# PIRprotov1.net
KiCad netlist of a schematic drawn in EAGLE
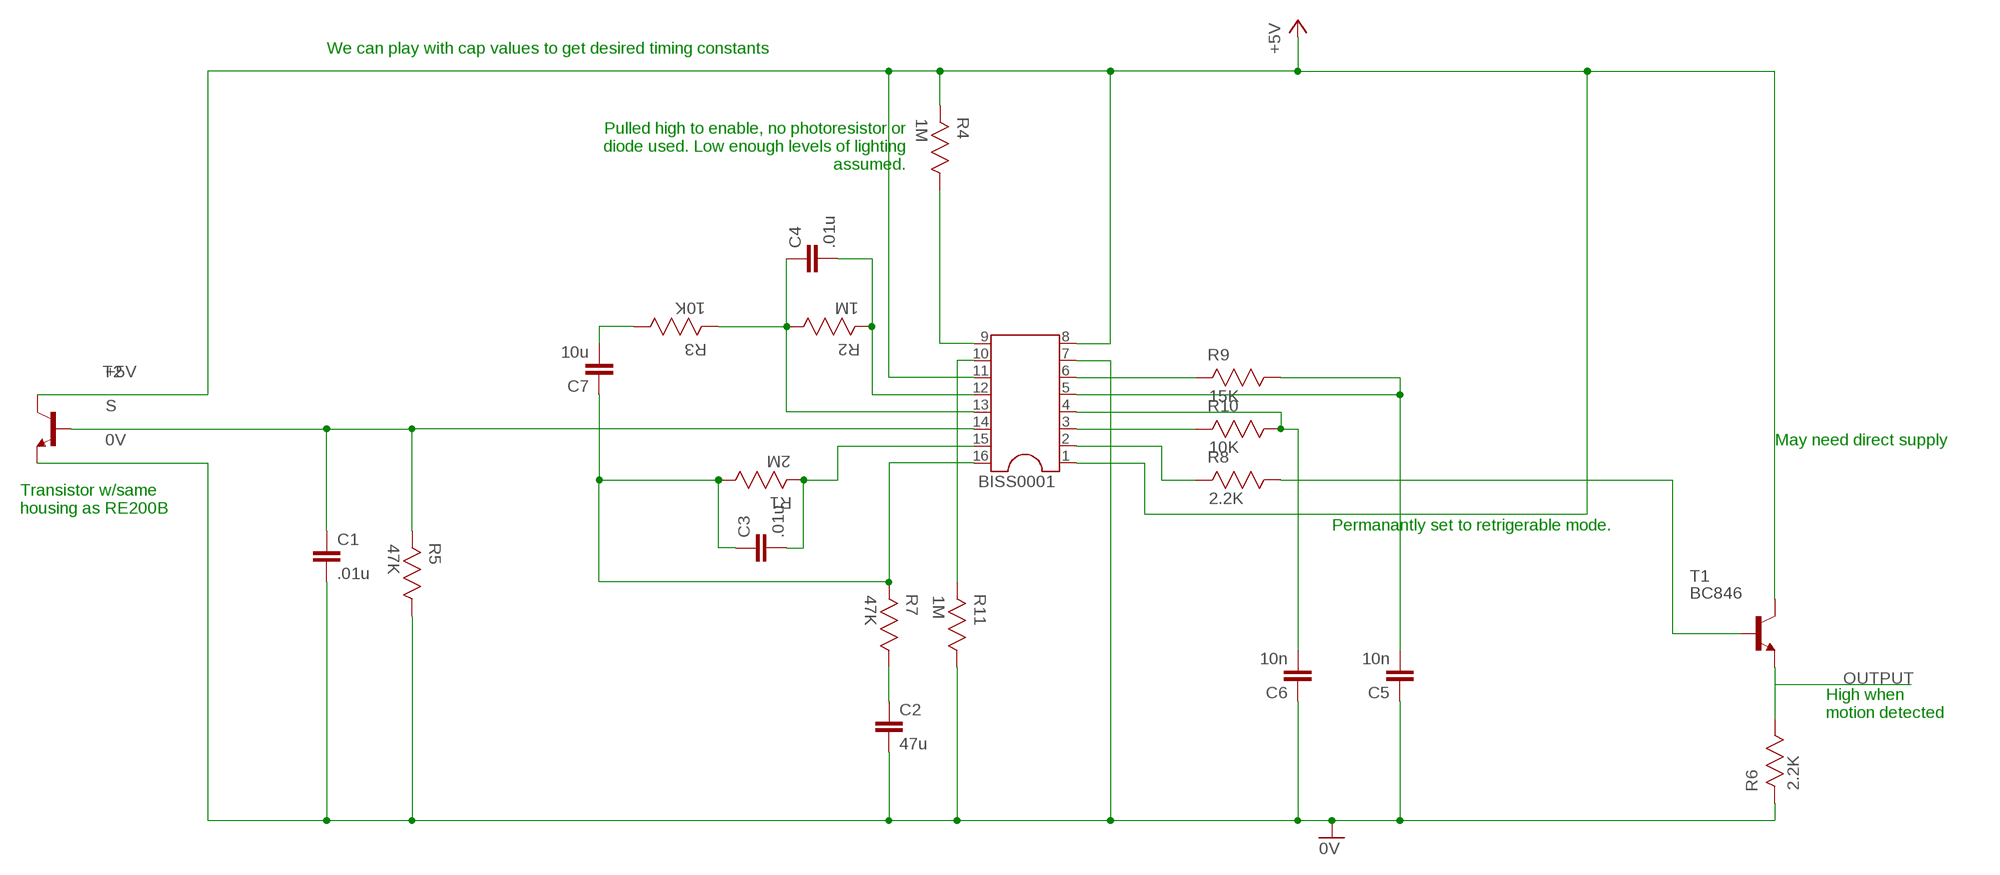
[diagram p0: schematic, sheet 1]

(export (version "E")
  (design (tool "Eeschema 10.0.6"))
  (components
    (comp (ref "BISS0001")
      (value "DIL16S")
      (footprint "eagle-import:SOCKET-16")
      (libsource (lib "eagle-import") (part "DIL16S"))
    )
    (comp (ref "C1")
      (value ".01u")
      (footprint "eagle-import:0805")
      (libsource (lib "eagle-import") (part "CAP0805"))
    )
    (comp (ref "C2")
      (value "47u")
      (footprint "eagle-import:0805")
      (libsource (lib "eagle-import") (part "CAP0805"))
    )
    (comp (ref "C3")
      (value ".01u")
      (footprint "eagle-import:0805")
      (libsource (lib "eagle-import") (part "CAP0805"))
    )
    (comp (ref "C4")
      (value ".01u")
      (footprint "eagle-import:0805")
      (libsource (lib "eagle-import") (part "CAP0805"))
    )
    (comp (ref "C5")
      (value "10n")
      (footprint "eagle-import:0805")
      (libsource (lib "eagle-import") (part "CAP0805"))
    )
    (comp (ref "C6")
      (value "10n")
      (footprint "eagle-import:0805")
      (libsource (lib "eagle-import") (part "CAP0805"))
    )
    (comp (ref "C7")
      (value "10u")
      (footprint "eagle-import:0805")
      (libsource (lib "eagle-import") (part "CAP0805"))
    )
    (comp (ref "R1")
      (value "2M")
      (footprint "eagle-import:0603RESISTOR")
      (fields (field (name "MPN") "CRCW06031K21FKEA") (field (name "TOLERANCE") "± 1.0 %"))
      (libsource (lib "eagle-import") (part "0603RESISTOR1"))
    )
    (comp (ref "R2")
      (value "1M")
      (footprint "eagle-import:0603RESISTOR")
      (fields (field (name "MPN") "CRCW06031K21FKEA") (field (name "TOLERANCE") "± 1.0 %"))
      (libsource (lib "eagle-import") (part "0603RESISTOR1"))
    )
    (comp (ref "R3")
      (value "10K")
      (footprint "eagle-import:0603RESISTOR")
      (fields (field (name "MPN") "CRCW06031K21FKEA") (field (name "TOLERANCE") "± 1.0 %"))
      (libsource (lib "eagle-import") (part "0603RESISTOR1"))
    )
    (comp (ref "R4")
      (value "1M")
      (footprint "eagle-import:0603RESISTOR")
      (fields (field (name "MPN") "CRCW06031K21FKEA") (field (name "TOLERANCE") "± 1.0 %"))
      (libsource (lib "eagle-import") (part "0603RESISTOR1"))
    )
    (comp (ref "R5")
      (value "47K")
      (footprint "eagle-import:0603RESISTOR")
      (fields (field (name "MPN") "CRCW06031K21FKEA") (field (name "TOLERANCE") "± 1.0 %"))
      (libsource (lib "eagle-import") (part "0603RESISTOR1"))
    )
    (comp (ref "R6")
      (value "2.2K")
      (footprint "eagle-import:0603RESISTOR")
      (fields (field (name "MPN") "CRCW06031K21FKEA") (field (name "TOLERANCE") "± 1.0 %"))
      (libsource (lib "eagle-import") (part "0603RESISTOR1"))
    )
    (comp (ref "R7")
      (value "47K")
      (footprint "eagle-import:0603RESISTOR")
      (fields (field (name "MPN") "CRCW06031K21FKEA") (field (name "TOLERANCE") "± 1.0 %"))
      (libsource (lib "eagle-import") (part "0603RESISTOR1"))
    )
    (comp (ref "R8")
      (value "2.2K")
      (footprint "eagle-import:0603RESISTOR")
      (fields (field (name "MPN") "CRCW06031K21FKEA") (field (name "TOLERANCE") "± 1.0 %"))
      (libsource (lib "eagle-import") (part "0603RESISTOR1"))
    )
    (comp (ref "R9")
      (value "15K")
      (footprint "eagle-import:0603RESISTOR")
      (fields (field (name "MPN") "CRCW06031K21FKEA") (field (name "TOLERANCE") "± 1.0 %"))
      (libsource (lib "eagle-import") (part "0603RESISTOR1"))
    )
    (comp (ref "R10")
      (value "10K")
      (footprint "eagle-import:0603RESISTOR")
      (fields (field (name "MPN") "CRCW06031K21FKEA") (field (name "TOLERANCE") "± 1.0 %"))
      (libsource (lib "eagle-import") (part "0603RESISTOR1"))
    )
    (comp (ref "R11")
      (value "1M")
      (footprint "eagle-import:0603RESISTOR")
      (fields (field (name "MPN") "CRCW06031K21FKEA") (field (name "TOLERANCE") "± 1.0 %"))
      (libsource (lib "eagle-import") (part "0603RESISTOR1"))
    )
    (comp (ref "T1")
      (value "BC846")
      (footprint "eagle-import:SOT23")
      (libsource (lib "eagle-import") (part "BC846"))
    )
    (comp (ref "T2")
      (value "-NPN-TO5")
      (footprint "eagle-import:TO5")
      (libsource (lib "eagle-import") (part "-NPN-TO5"))
    )
  )
  (nets
    (net (code "1") (name "+5V") (class "Default")
      (node (ref "BISS0001") (pin "1") (pinfunction "1_1") (pintype "passive"))
      (node (ref "BISS0001") (pin "11") (pinfunction "11_11") (pintype "passive"))
      (node (ref "BISS0001") (pin "8") (pinfunction "8_8") (pintype "passive"))
      (node (ref "R4") (pin "2") (pinfunction "2_2") (pintype "passive"))
      (node (ref "T1") (pin "3") (pinfunction "C_3") (pintype "passive"))
      (node (ref "T2") (pin "3") (pinfunction "C_3") (pintype "passive"))
    )
    (net (code "2") (name "/OUTPUT") (class "Default")
      (node (ref "R6") (pin "1") (pinfunction "1_1") (pintype "passive"))
      (node (ref "T1") (pin "2") (pinfunction "E_2") (pintype "passive"))
    )
    (net (code "3") (name "/S") (class "Default")
      (node (ref "BISS0001") (pin "14") (pinfunction "14_14") (pintype "passive"))
      (node (ref "C1") (pin "1") (pinfunction "1_1") (pintype "passive"))
      (node (ref "R5") (pin "2") (pinfunction "2_2") (pintype "passive"))
      (node (ref "T2") (pin "2") (pinfunction "B_2") (pintype "passive"))
    )
    (net (code "4") (name "0V") (class "Default")
      (node (ref "BISS0001") (pin "7") (pinfunction "7_7") (pintype "passive"))
      (node (ref "C1") (pin "2") (pinfunction "2_2") (pintype "passive"))
      (node (ref "C2") (pin "2") (pinfunction "2_2") (pintype "passive"))
      (node (ref "C5") (pin "1") (pinfunction "1_1") (pintype "passive"))
      (node (ref "C6") (pin "1") (pinfunction "1_1") (pintype "passive"))
      (node (ref "R11") (pin "1") (pinfunction "1_1") (pintype "passive"))
      (node (ref "R5") (pin "1") (pinfunction "1_1") (pintype "passive"))
      (node (ref "R6") (pin "2") (pinfunction "2_2") (pintype "passive"))
      (node (ref "T2") (pin "1") (pinfunction "E_1") (pintype "passive"))
    )
    (net (code "5") (name "Net-(BISS0001-Pad2)") (class "Default")
      (node (ref "BISS0001") (pin "2") (pinfunction "2_2") (pintype "passive"))
      (node (ref "R8") (pin "2") (pinfunction "2_2") (pintype "passive"))
    )
    (net (code "6") (name "Net-(BISS0001-Pad3)") (class "Default")
      (node (ref "BISS0001") (pin "3") (pinfunction "3_3") (pintype "passive"))
      (node (ref "R10") (pin "2") (pinfunction "2_2") (pintype "passive"))
    )
    (net (code "7") (name "Net-(BISS0001-Pad4)") (class "Default")
      (node (ref "BISS0001") (pin "4") (pinfunction "4_4") (pintype "passive"))
      (node (ref "C6") (pin "2") (pinfunction "2_2") (pintype "passive"))
      (node (ref "R10") (pin "1") (pinfunction "1_1") (pintype "passive"))
    )
    (net (code "8") (name "Net-(BISS0001-Pad5)") (class "Default")
      (node (ref "BISS0001") (pin "5") (pinfunction "5_5") (pintype "passive"))
      (node (ref "C5") (pin "2") (pinfunction "2_2") (pintype "passive"))
      (node (ref "R9") (pin "1") (pinfunction "1_1") (pintype "passive"))
    )
    (net (code "9") (name "Net-(BISS0001-Pad6)") (class "Default")
      (node (ref "BISS0001") (pin "6") (pinfunction "6_6") (pintype "passive"))
      (node (ref "R9") (pin "2") (pinfunction "2_2") (pintype "passive"))
    )
    (net (code "10") (name "Net-(BISS0001-Pad9)") (class "Default")
      (node (ref "BISS0001") (pin "9") (pinfunction "9_9") (pintype "passive"))
      (node (ref "R4") (pin "1") (pinfunction "1_1") (pintype "passive"))
    )
    (net (code "11") (name "Net-(BISS0001-Pad10)") (class "Default")
      (node (ref "BISS0001") (pin "10") (pinfunction "10_10") (pintype "passive"))
      (node (ref "R11") (pin "2") (pinfunction "2_2") (pintype "passive"))
    )
    (net (code "12") (name "Net-(BISS0001-Pad12)") (class "Default")
      (node (ref "BISS0001") (pin "12") (pinfunction "12_12") (pintype "passive"))
      (node (ref "C4") (pin "2") (pinfunction "2_2") (pintype "passive"))
      (node (ref "R2") (pin "2") (pinfunction "2_2") (pintype "passive"))
    )
    (net (code "13") (name "Net-(BISS0001-Pad13)") (class "Default")
      (node (ref "BISS0001") (pin "13") (pinfunction "13_13") (pintype "passive"))
      (node (ref "C4") (pin "1") (pinfunction "1_1") (pintype "passive"))
      (node (ref "R2") (pin "1") (pinfunction "1_1") (pintype "passive"))
      (node (ref "R3") (pin "2") (pinfunction "2_2") (pintype "passive"))
    )
    (net (code "14") (name "Net-(BISS0001-Pad15)") (class "Default")
      (node (ref "BISS0001") (pin "15") (pinfunction "15_15") (pintype "passive"))
      (node (ref "C3") (pin "2") (pinfunction "2_2") (pintype "passive"))
      (node (ref "R1") (pin "2") (pinfunction "2_2") (pintype "passive"))
    )
    (net (code "15") (name "Net-(BISS0001-Pad16)") (class "Default")
      (node (ref "BISS0001") (pin "16") (pinfunction "16_16") (pintype "passive"))
      (node (ref "C3") (pin "1") (pinfunction "1_1") (pintype "passive"))
      (node (ref "C7") (pin "1") (pinfunction "1_1") (pintype "passive"))
      (node (ref "R1") (pin "1") (pinfunction "1_1") (pintype "passive"))
      (node (ref "R7") (pin "2") (pinfunction "2_2") (pintype "passive"))
    )
    (net (code "16") (name "Net-(C2-Pad1)") (class "Default")
      (node (ref "C2") (pin "1") (pinfunction "1_1") (pintype "passive"))
      (node (ref "R7") (pin "1") (pinfunction "1_1") (pintype "passive"))
    )
    (net (code "17") (name "Net-(C7-Pad2)") (class "Default")
      (node (ref "C7") (pin "2") (pinfunction "2_2") (pintype "passive"))
      (node (ref "R3") (pin "1") (pinfunction "1_1") (pintype "passive"))
    )
    (net (code "18") (name "Net-(T1-B)") (class "Default")
      (node (ref "R8") (pin "1") (pinfunction "1_1") (pintype "passive"))
      (node (ref "T1") (pin "1") (pinfunction "B_1") (pintype "passive"))
    )
  )
)
